# 4_-_Ethernet_PHY.net
KiCad netlist of a schematic drawn in Altium Designer
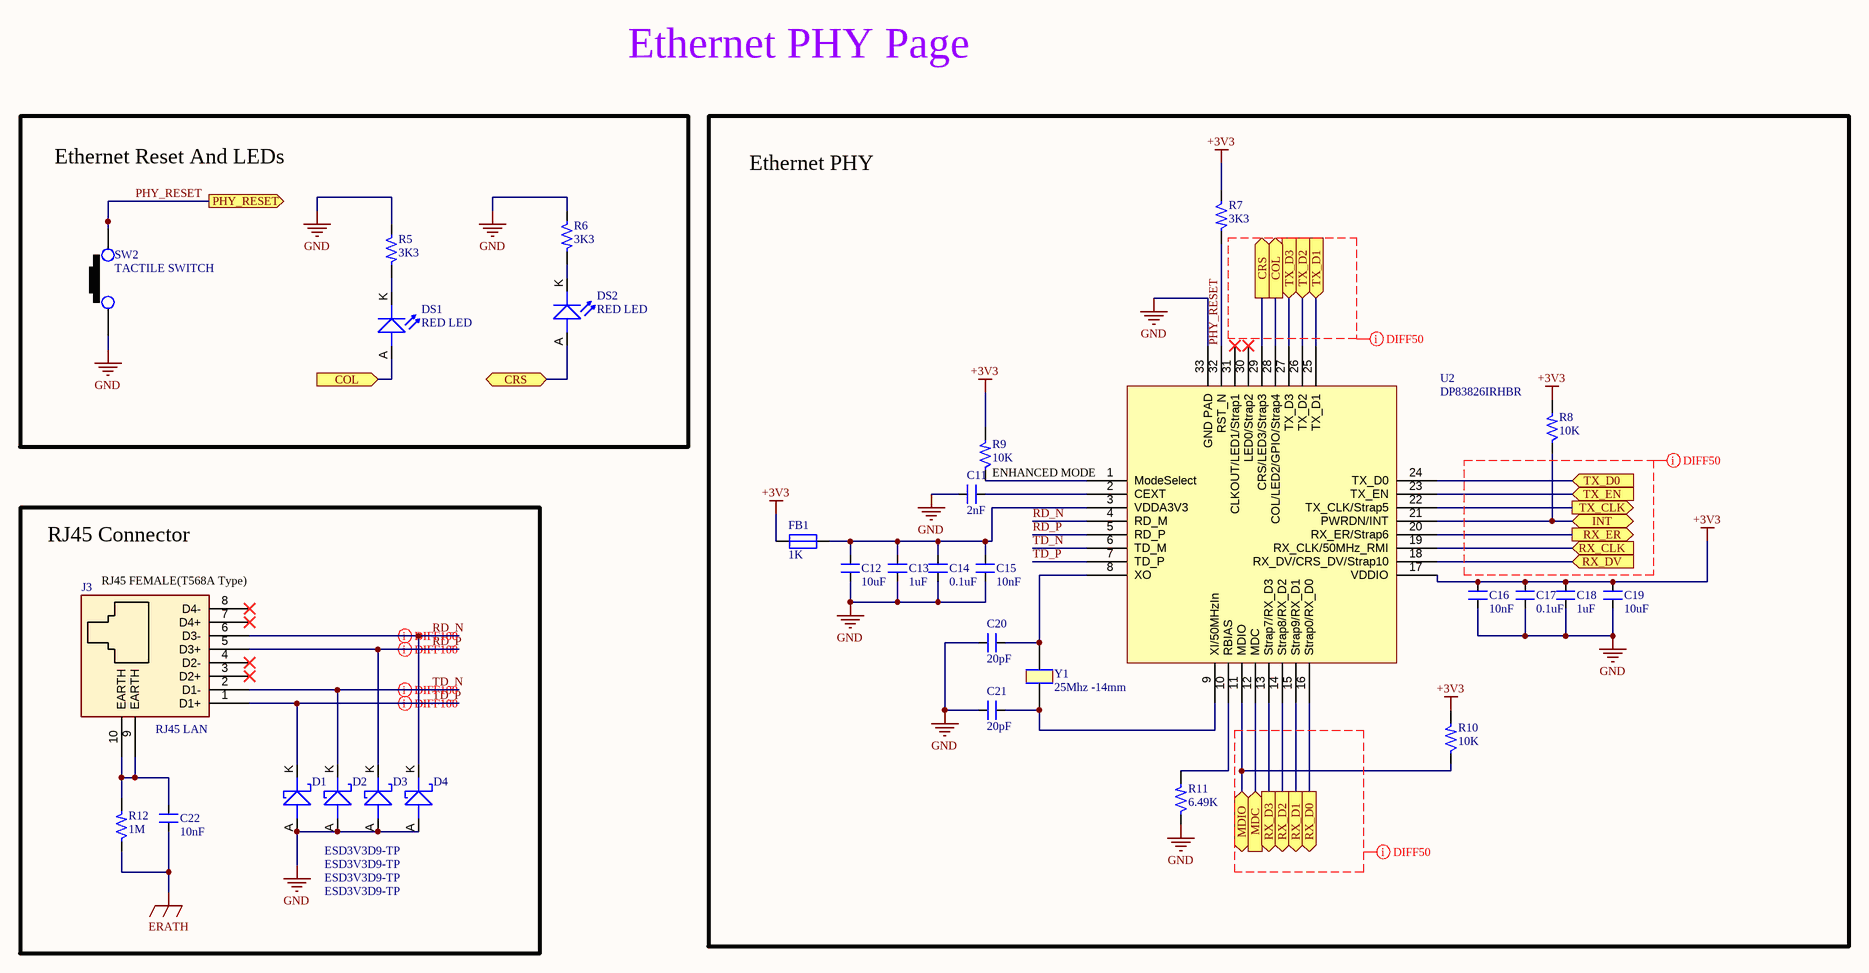
[diagram p0: [4] - Ethernet PHY.SchDoc]

(export (version "E")
  (design (tool "Eeschema 10.0.6"))
  (components
    (comp (ref "C11")
      (value "2nF")
      (footprint "CAP_0805")
      (description "2000pF ±10% 50V Ceramic Capacitor X7R 0805 (2012 Metric)")
      (fields
        (field (name "MANUFACTURER") "Samsung Electro-Mechanics")
        (field (name "MANUFACTURER PART NUMBER") "CL21B202KBANNNC")
      )
      (libsource (lib "ESTEEMPCBLIB") (part "CAP_2nF-50V-10%-0805"))
    )
    (comp (ref "C12")
      (value "10uF")
      (footprint "CAP_1206")
      (description "10µF ±10% 50V Ceramic Capacitor X7R 1206 (3216 Metric)")
      (fields
        (field (name "MANUFACTURER") "KEMET")
        (field (name "MANUFACTURER PART NUMBER") "CL31B106KBHNNNE")
      )
      (libsource (lib "ESTEEMPCBLIB") (part "CAP_10uF-50V-10%-1206"))
    )
    (comp (ref "C13")
      (value "1uF")
      (footprint "CAP_0805")
      (description "1µF ±5% 50V Ceramic Capacitor X7R 0805 (2012 Metric)")
      (fields
        (field (name "MANUFACTURER") "Samsung")
        (field (name "MANUFACTURER PART NUMBER") "CC0805JKX7R9BB105")
      )
      (libsource (lib "ESTEEMPCBLIB") (part "CAP_1uF-50V-5%-0805"))
    )
    (comp (ref "C14")
      (value "0.1uF")
      (footprint "CAP_0805")
      (description "0.1µF ±10% 50V Ceramic Capacitor X7R 0805 (2012 Metric)")
      (fields
        (field (name "MANUFACTURER") "Samsung")
        (field (name "MANUFACTURER PART NUMBER") "CL21B104KBCNNNC")
      )
      (libsource (lib "ESTEEMPCBLIB") (part "CAP_0.1uF-50V-10%-0805"))
    )
    (comp (ref "C15")
      (value "10nF")
      (footprint "CAP_0805")
      (description "10000pF ±10% 50V Ceramic Capacitor X7R 0805 (2012 Metric)")
      (fields
        (field (name "MANUFACTURER") "Samsung")
        (field (name "MANUFACTURER PART NUMBER") "C0805C103K5RECAUTO")
      )
      (libsource (lib "ESTEEMPCBLIB") (part "CAP_10nF-50V-10%-0805"))
    )
    (comp (ref "C16")
      (value "10nF")
      (footprint "CAP_0805")
      (description "10000pF ±10% 50V Ceramic Capacitor X7R 0805 (2012 Metric)")
      (fields
        (field (name "MANUFACTURER") "Samsung")
        (field (name "MANUFACTURER PART NUMBER") "C0805C103K5RECAUTO")
      )
      (libsource (lib "ESTEEMPCBLIB") (part "CAP_10nF-50V-10%-0805"))
    )
    (comp (ref "C17")
      (value "0.1uF")
      (footprint "CAP_0805")
      (description "0.1µF ±10% 50V Ceramic Capacitor X7R 0805 (2012 Metric)")
      (fields
        (field (name "MANUFACTURER") "Samsung")
        (field (name "MANUFACTURER PART NUMBER") "CL21B104KBCNNNC")
      )
      (libsource (lib "ESTEEMPCBLIB") (part "CAP_0.1uF-50V-10%-0805"))
    )
    (comp (ref "C18")
      (value "1uF")
      (footprint "CAP_0805")
      (description "1µF ±5% 50V Ceramic Capacitor X7R 0805 (2012 Metric)")
      (fields
        (field (name "MANUFACTURER") "Samsung")
        (field (name "MANUFACTURER PART NUMBER") "CC0805JKX7R9BB105")
      )
      (libsource (lib "ESTEEMPCBLIB") (part "CAP_1uF-50V-5%-0805"))
    )
    (comp (ref "C19")
      (value "10uF")
      (footprint "CAP_1206")
      (description "10µF ±10% 50V Ceramic Capacitor X7R 1206 (3216 Metric)")
      (fields
        (field (name "MANUFACTURER") "KEMET")
        (field (name "MANUFACTURER PART NUMBER") "CL31B106KBHNNNE")
      )
      (libsource (lib "ESTEEMPCBLIB") (part "CAP_10uF-50V-10%-1206"))
    )
    (comp (ref "C20")
      (value "20pF")
      (footprint "CAP_0805")
      (description "±10% 50V Ceramic Capacitor C0G, NP0 0805 (2012 Metric)")
      (fields
        (field (name "MANUFACTURER") "AVX Corporation")
        (field (name "MANUFACTURER PART NUMBER") "08055A200KAT2A")
      )
      (libsource (lib "ESTEEMPCBLIB") (part "CAP_20pF-50V-10%-0805"))
    )
    (comp (ref "C21")
      (value "20pF")
      (footprint "CAP_0805")
      (description "±10% 50V Ceramic Capacitor C0G, NP0 0805 (2012 Metric)")
      (fields
        (field (name "MANUFACTURER") "AVX Corporation")
        (field (name "MANUFACTURER PART NUMBER") "08055A200KAT2A")
      )
      (libsource (lib "ESTEEMPCBLIB") (part "CAP_20pF-50V-10%-0805"))
    )
    (comp (ref "C22")
      (value "10nF")
      (footprint "CAP_P196_102X287_H332_RAD_TH")
      (description "10000pF ±10% 1000V (1kV) Ceramic Capacitor X7R Radial")
      (fields
        (field (name "MANUFACTURER") "Yageo")
        (field (name "MANUFACTURER PART NUMBER") "RDER73A103K2K1H03B")
      )
      (libsource (lib "ESTEEMPCBLIB") (part "CAP_10nF-1KV-10%-RAD-TH"))
    )
    (comp (ref "D1")
      (value "ESD3V3D9-TP")
      (footprint "DIO_SOD-923")
      (description "8.8V Clamp 5A (8/20µs) Ipp Tvs Diode Surface Mount SOD-923")
      (fields (field (name "MANUFACTURER") "Micro Commercial Co"))
      (libsource (lib "ESTEEMPCBLIB") (part "DIO-T_3.3V-8.8V-SOD923"))
    )
    (comp (ref "D2")
      (value "ESD3V3D9-TP")
      (footprint "DIO_SOD-923")
      (description "8.8V Clamp 5A (8/20µs) Ipp Tvs Diode Surface Mount SOD-923")
      (fields (field (name "MANUFACTURER") "Micro Commercial Co"))
      (libsource (lib "ESTEEMPCBLIB") (part "DIO-T_3.3V-8.8V-SOD923"))
    )
    (comp (ref "D3")
      (value "ESD3V3D9-TP")
      (footprint "DIO_SOD-923")
      (description "8.8V Clamp 5A (8/20µs) Ipp Tvs Diode Surface Mount SOD-923")
      (fields (field (name "MANUFACTURER") "Micro Commercial Co"))
      (libsource (lib "ESTEEMPCBLIB") (part "DIO-T_3.3V-8.8V-SOD923"))
    )
    (comp (ref "D4")
      (value "ESD3V3D9-TP")
      (footprint "DIO_SOD-923")
      (description "8.8V Clamp 5A (8/20µs) Ipp Tvs Diode Surface Mount SOD-923")
      (fields (field (name "MANUFACTURER") "Micro Commercial Co"))
      (libsource (lib "ESTEEMPCBLIB") (part "DIO-T_3.3V-8.8V-SOD923"))
    )
    (comp (ref "DS1")
      (value "RED LED")
      (footprint "LED_0805")
      (description "Red 631nm LED Indication - Discrete 2V 0805 (2012 Metric)")
      (fields
        (field (name "MANUFACTURER") "Vishay Lite-On")
        (field (name "MANUFACTURER PART NUMBER") "LTST-C171KRKT")
      )
      (libsource (lib "ESTEEMPCBLIB") (part "LED_RED-2V-20mA-0805"))
    )
    (comp (ref "DS2")
      (value "RED LED")
      (footprint "LED_0805")
      (description "Red 631nm LED Indication - Discrete 2V 0805 (2012 Metric)")
      (fields
        (field (name "MANUFACTURER") "Vishay Lite-On")
        (field (name "MANUFACTURER PART NUMBER") "LTST-C171KRKT")
      )
      (libsource (lib "ESTEEMPCBLIB") (part "LED_RED-2V-20mA-0805"))
    )
    (comp (ref "FB1")
      (value "1K")
      (footprint "IND_0805")
      (description "1 kOhms @ 100MHz 1 Power Line Ferrite Bead 0805 (2012 Metric) 1.6A")
      (fields
        (field (name "MANUFACTURER") "Laird")
        (field (name "MANUFACTURER PART NUMBER") "BLM21SP102SH1D")
      )
      (libsource (lib "ESTEEMPCBLIB") (part "FB_1K-100MHZ-1.6A-0805"))
    )
    (comp (ref "J3")
      (value "RJ45 LAN")
      (footprint "CON10_P106_RJ45_TH_ST")
      (description "8 Pins, 2 Row 2.54mm Pitch, right angle Connector, male")
      (fields
        (field (name "MANUFACTURER") "Assmann")
        (field (name "MANUFACTURER PART NUMBER") "A-2004-2-4-LPS-N-R")
      )
      (libsource (lib "ESTEEMPCBLIB") (part "CON-SKT-RJ_8C8P-RA-TH"))
    )
    (comp (ref "R5")
      (value "3K3")
      (footprint "RES_0603")
      (description "3.3 kOhms ±1% 0.1W, 1/10W Chip Resistor 0603 (1608 Metric) Automotive AEC-Q200 Thick Film")
      (fields (field (name "MANUFACTURER") "Wilson") (field (name "MANUFACTURER PART NUMBER") "WR06X3301FTL"))
      (libsource (lib "ESTEEMPCBLIB") (part "RES_3.3K-0.1W-1%-0603"))
    )
    (comp (ref "R6")
      (value "3K3")
      (footprint "RES_0603")
      (description "3.3 kOhms ±1% 0.1W, 1/10W Chip Resistor 0603 (1608 Metric) Automotive AEC-Q200 Thick Film")
      (fields (field (name "MANUFACTURER") "Wilson") (field (name "MANUFACTURER PART NUMBER") "WR06X3301FTL"))
      (libsource (lib "ESTEEMPCBLIB") (part "RES_3.3K-0.1W-1%-0603"))
    )
    (comp (ref "R7")
      (value "3K3")
      (footprint "RES_0603")
      (description "3.3 kOhms ±1% 0.1W, 1/10W Chip Resistor 0603 (1608 Metric) Automotive AEC-Q200 Thick Film")
      (fields (field (name "MANUFACTURER") "Wilson") (field (name "MANUFACTURER PART NUMBER") "WR06X3301FTL"))
      (libsource (lib "ESTEEMPCBLIB") (part "RES_3.3K-0.1W-1%-0603"))
    )
    (comp (ref "R8")
      (value "10K")
      (footprint "RES_0603")
      (description "10 kOhms ±1% 0.1W, 1/10W Chip Resistor 0603 (1608 Metric) Automotive AEC-Q200 Thick Film")
      (fields (field (name "MANUFACTURER") "Walsin") (field (name "MANUFACTURER PART NUMBER") "WR06X1002FTL"))
      (libsource (lib "ESTEEMPCBLIB") (part "RES_10K-0.1W-1%-0603"))
    )
    (comp (ref "R9")
      (value "10K")
      (footprint "RES_0603")
      (description "10 kOhms ±1% 0.1W, 1/10W Chip Resistor 0603 (1608 Metric) Automotive AEC-Q200 Thick Film")
      (fields (field (name "MANUFACTURER") "Walsin") (field (name "MANUFACTURER PART NUMBER") "WR06X1002FTL"))
      (libsource (lib "ESTEEMPCBLIB") (part "RES_10K-0.1W-1%-0603"))
    )
    (comp (ref "R10")
      (value "10K")
      (footprint "RES_0603")
      (description "10 kOhms ±1% 0.1W, 1/10W Chip Resistor 0603 (1608 Metric) Automotive AEC-Q200 Thick Film")
      (fields (field (name "MANUFACTURER") "Walsin") (field (name "MANUFACTURER PART NUMBER") "WR06X1002FTL"))
      (libsource (lib "ESTEEMPCBLIB") (part "RES_10K-0.1W-1%-0603"))
    )
    (comp (ref "R11")
      (value "6.49K")
      (footprint "RES_0805")
      (description "6.49 kOhms ±1% 0.125W, 1/8W Chip Resistor 0805 (2012 Metric) Moisture Resistant Thick Film")
      (fields
        (field (name "MANUFACTURER") "Stackpole Electronics")
        (field (name "MANUFACTURER PART NUMBER") "RC0805FR-076K49L")
      )
      (libsource (lib "ESTEEMPCBLIB") (part "RES_6.49K-0.125W-1%-0805"))
    )
    (comp (ref "R12")
      (value "1M")
      (footprint "RES_1206")
      (fields (field (name "MANUFACTURER") "Walsin") (field (name "MANUFACTURER PART NUMBER") "WR12X1004FTL"))
      (libsource (lib "ESTEEMPCBLIB") (part "RES_1M-0.25W-1%-1206"))
    )
    (comp (ref "SW2")
      (value "TACTILE SWITCH")
      (footprint "SW_342_SMD")
      (description "Tactile Switch SPST-NO Top Actuated Surface Mount")
      (fields
        (field (name "MANUFACTURER") "ITT C&K")
        (field (name "MANUFACTURER PART NUMBER") "RS-282G05A3-SMRT")
      )
      (libsource (lib "ESTEEMPCBLIB") (part "SW1_RS-282G05A3-SMRT-SMD"))
    )
    (comp (ref "U2")
      (value "DP83826IRHBR")
      (footprint "VQFN32_19_218_23X9_SMD")
      (fields (field (name "MANUFACTURER") "Texas Instruments"))
      (libsource (lib "ESTEEMPCBLIB") (part "IC_DP83826IRHBR"))
    )
    (comp (ref "Y1")
      (value "25Mhz -14mm")
      (footprint "XTAL_314_240X47_SMD")
      (description "25MHz ±30ppm Crystal 20pF 30 Ohms HC-49/US")
      (fields
        (field (name "MANUFACTURER") "Abracon")
        (field (name "MANUFACTURER PART NUMBER") "FOXSDLF/250F-20")
      )
      (libsource (lib "ESTEEMPCBLIB") (part "XTAL_25Mhz-FOXSDLF/250F-20"))
    )
  )
  (nets
    (net (code "1") (name "+3V3") (class "Default")
      (node (ref "C16") (pin "1") (pinfunction "1_1") (pintype "passive"))
      (node (ref "C17") (pin "1") (pinfunction "1_1") (pintype "passive"))
      (node (ref "C18") (pin "1") (pinfunction "1_1") (pintype "passive"))
      (node (ref "C19") (pin "1") (pinfunction "1_1") (pintype "passive"))
      (node (ref "FB1") (pin "1") (pinfunction "1_1") (pintype "passive"))
      (node (ref "R10") (pin "2") (pinfunction "2_2") (pintype "passive"))
      (node (ref "R7") (pin "1") (pinfunction "1_1") (pintype "passive"))
      (node (ref "R8") (pin "2") (pinfunction "2_2") (pintype "passive"))
      (node (ref "R9") (pin "2") (pinfunction "2_2") (pintype "passive"))
      (node (ref "U2") (pin "17") (pinfunction "VDDIO_17") (pintype "passive"))
    )
    (net (code "2") (name "/COL") (class "Default")
      (node (ref "DS1") (pin "A") (pinfunction "ANODE_A") (pintype "passive"))
      (node (ref "U2") (pin "28") (pinfunction "COL/LED2/GPIO/Strap4_28") (pintype "passive"))
    )
    (net (code "3") (name "/CRS") (class "Default")
      (node (ref "DS2") (pin "A") (pinfunction "ANODE_A") (pintype "passive"))
      (node (ref "U2") (pin "29") (pinfunction "CRS/LED3/Strap3_29") (pintype "passive"))
    )
    (net (code "4") (name "/INT") (class "Default")
      (node (ref "R8") (pin "1") (pinfunction "1_1") (pintype "passive"))
      (node (ref "U2") (pin "21") (pinfunction "PWRDN/INT_21") (pintype "passive"))
    )
    (net (code "5") (name "/MDC") (class "Default")
      (node (ref "U2") (pin "12") (pinfunction "MDC_12") (pintype "passive"))
    )
    (net (code "6") (name "/MDIO") (class "Default")
      (node (ref "R10") (pin "1") (pinfunction "1_1") (pintype "passive"))
      (node (ref "U2") (pin "11") (pinfunction "MDIO_11") (pintype "passive"))
    )
    (net (code "7") (name "/PHY_RESET") (class "Default")
      (node (ref "R7") (pin "2") (pinfunction "2_2") (pintype "passive"))
      (node (ref "SW2") (pin "2") (pinfunction "2_2") (pintype "passive"))
      (node (ref "U2") (pin "32") (pinfunction "RST_N_32") (pintype "passive"))
    )
    (net (code "8") (name "/RD_N") (class "Default")
      (node (ref "D4") (pin "K") (pinfunction "K_K") (pintype "passive"))
      (node (ref "J3") (pin "6") (pinfunction "D3-_6") (pintype "passive"))
      (node (ref "U2") (pin "4") (pinfunction "RD_M_4") (pintype "passive"))
    )
    (net (code "9") (name "/RD_P") (class "Default")
      (node (ref "D3") (pin "K") (pinfunction "K_K") (pintype "passive"))
      (node (ref "J3") (pin "5") (pinfunction "D3+_5") (pintype "passive"))
      (node (ref "U2") (pin "5") (pinfunction "RD_P_5") (pintype "passive"))
    )
    (net (code "10") (name "/RX_CLK") (class "Default")
      (node (ref "U2") (pin "19") (pinfunction "RX_CLK/50MHz_RMI_19") (pintype "passive"))
    )
    (net (code "11") (name "/RX_D0") (class "Default")
      (node (ref "U2") (pin "16") (pinfunction "Strap0/RX_D0_16") (pintype "passive"))
    )
    (net (code "12") (name "/RX_D1") (class "Default")
      (node (ref "U2") (pin "15") (pinfunction "Strap9/RX_D1_15") (pintype "passive"))
    )
    (net (code "13") (name "/RX_D2") (class "Default")
      (node (ref "U2") (pin "14") (pinfunction "Strap8/RX_D2_14") (pintype "passive"))
    )
    (net (code "14") (name "/RX_D3") (class "Default")
      (node (ref "U2") (pin "13") (pinfunction "Strap7/RX_D3_13") (pintype "passive"))
    )
    (net (code "15") (name "/RX_DV") (class "Default")
      (node (ref "U2") (pin "18") (pinfunction "RX_DV/CRS_DV/Strap10_18") (pintype "passive"))
    )
    (net (code "16") (name "/RX_ER") (class "Default")
      (node (ref "U2") (pin "20") (pinfunction "RX_ER/Strap6_20") (pintype "passive"))
    )
    (net (code "17") (name "/TD_N") (class "Default")
      (node (ref "D2") (pin "K") (pinfunction "K_K") (pintype "passive"))
      (node (ref "J3") (pin "2") (pinfunction "D1-_2") (pintype "passive"))
      (node (ref "U2") (pin "6") (pinfunction "TD_M_6") (pintype "passive"))
    )
    (net (code "18") (name "/TD_P") (class "Default")
      (node (ref "D1") (pin "K") (pinfunction "K_K") (pintype "passive"))
      (node (ref "J3") (pin "1") (pinfunction "D1+_1") (pintype "passive"))
      (node (ref "U2") (pin "7") (pinfunction "TD_P_7") (pintype "passive"))
    )
    (net (code "19") (name "/TX_CLK") (class "Default")
      (node (ref "U2") (pin "22") (pinfunction "TX_CLK/Strap5_22") (pintype "passive"))
    )
    (net (code "20") (name "/TX_D0") (class "Default")
      (node (ref "U2") (pin "24") (pinfunction "TX_D0_24") (pintype "passive"))
    )
    (net (code "21") (name "/TX_D1") (class "Default")
      (node (ref "U2") (pin "25") (pinfunction "TX_D1_25") (pintype "passive"))
    )
    (net (code "22") (name "/TX_D2") (class "Default")
      (node (ref "U2") (pin "26") (pinfunction "TX_D2_26") (pintype "passive"))
    )
    (net (code "23") (name "/TX_D3") (class "Default")
      (node (ref "U2") (pin "27") (pinfunction "TX_D3_27") (pintype "passive"))
    )
    (net (code "24") (name "/TX_EN") (class "Default")
      (node (ref "U2") (pin "23") (pinfunction "TX_EN_23") (pintype "passive"))
    )
    (net (code "25") (name "ERATH") (class "Default")
      (node (ref "C22") (pin "1") (pinfunction "1_1") (pintype "passive"))
      (node (ref "R12") (pin "1") (pinfunction "1_1") (pintype "passive"))
    )
    (net (code "26") (name "GND") (class "Default")
      (node (ref "C11") (pin "1") (pinfunction "1_1") (pintype "passive"))
      (node (ref "C12") (pin "1") (pinfunction "1_1") (pintype "passive"))
      (node (ref "C13") (pin "1") (pinfunction "1_1") (pintype "passive"))
      (node (ref "C14") (pin "1") (pinfunction "1_1") (pintype "passive"))
      (node (ref "C15") (pin "1") (pinfunction "1_1") (pintype "passive"))
      (node (ref "C16") (pin "2") (pinfunction "2_2") (pintype "passive"))
      (node (ref "C17") (pin "2") (pinfunction "2_2") (pintype "passive"))
      (node (ref "C18") (pin "2") (pinfunction "2_2") (pintype "passive"))
      (node (ref "C19") (pin "2") (pinfunction "2_2") (pintype "passive"))
      (node (ref "C20") (pin "1") (pinfunction "1_1") (pintype "passive"))
      (node (ref "C21") (pin "1") (pinfunction "1_1") (pintype "passive"))
      (node (ref "D1") (pin "A") (pinfunction "A_A") (pintype "passive"))
      (node (ref "D2") (pin "A") (pinfunction "A_A") (pintype "passive"))
      (node (ref "D3") (pin "A") (pinfunction "A_A") (pintype "passive"))
      (node (ref "D4") (pin "A") (pinfunction "A_A") (pintype "passive"))
      (node (ref "R11") (pin "1") (pinfunction "1_1") (pintype "passive"))
      (node (ref "R5") (pin "1") (pinfunction "1_1") (pintype "passive"))
      (node (ref "R6") (pin "1") (pinfunction "1_1") (pintype "passive"))
      (node (ref "SW2") (pin "1") (pinfunction "1_1") (pintype "passive"))
      (node (ref "U2") (pin "33") (pinfunction "GND_PAD_33") (pintype "passive"))
    )
    (net (code "27") (name "Net-(C22-Pad2)") (class "Default")
      (node (ref "C22") (pin "2") (pinfunction "2_2") (pintype "passive"))
      (node (ref "J3") (pin "10") (pinfunction "EARTH_10") (pintype "passive"))
      (node (ref "J3") (pin "9") (pinfunction "EARTH_9") (pintype "passive"))
      (node (ref "R12") (pin "2") (pinfunction "2_2") (pintype "passive"))
    )
    (net (code "28") (name "Net-(DS1-CATHODE)") (class "Default")
      (node (ref "DS1") (pin "K") (pinfunction "CATHODE_K") (pintype "passive"))
      (node (ref "R5") (pin "2") (pinfunction "2_2") (pintype "passive"))
    )
    (net (code "29") (name "Net-(DS2-CATHODE)") (class "Default")
      (node (ref "DS2") (pin "K") (pinfunction "CATHODE_K") (pintype "passive"))
      (node (ref "R6") (pin "2") (pinfunction "2_2") (pintype "passive"))
    )
    (net (code "30") (name "Net-(U2-CEXT)") (class "Default")
      (node (ref "C11") (pin "2") (pinfunction "2_2") (pintype "passive"))
      (node (ref "U2") (pin "2") (pinfunction "CEXT_2") (pintype "passive"))
    )
    (net (code "31") (name "Net-(U2-ModeSelect)") (class "Default")
      (node (ref "R9") (pin "1") (pinfunction "1_1") (pintype "passive"))
      (node (ref "U2") (pin "1") (pinfunction "ModeSelect_1") (pintype "passive"))
    )
    (net (code "32") (name "Net-(U2-RBIAS)") (class "Default")
      (node (ref "R11") (pin "2") (pinfunction "2_2") (pintype "passive"))
      (node (ref "U2") (pin "10") (pinfunction "RBIAS_10") (pintype "passive"))
    )
    (net (code "33") (name "Net-(U2-VDDA3V3)") (class "Default")
      (node (ref "C12") (pin "2") (pinfunction "2_2") (pintype "passive"))
      (node (ref "C13") (pin "2") (pinfunction "2_2") (pintype "passive"))
      (node (ref "C14") (pin "2") (pinfunction "2_2") (pintype "passive"))
      (node (ref "C15") (pin "2") (pinfunction "2_2") (pintype "passive"))
      (node (ref "FB1") (pin "2") (pinfunction "2_2") (pintype "passive"))
      (node (ref "U2") (pin "3") (pinfunction "VDDA3V3_3") (pintype "passive"))
    )
    (net (code "34") (name "Net-(U2-XI{slash}50MHzIn)") (class "Default")
      (node (ref "C21") (pin "2") (pinfunction "2_2") (pintype "passive"))
      (node (ref "U2") (pin "9") (pinfunction "XI/50MHzIn_9") (pintype "passive"))
      (node (ref "Y1") (pin "1") (pinfunction "1_1") (pintype "passive"))
    )
    (net (code "35") (name "Net-(U2-XO)") (class "Default")
      (node (ref "C20") (pin "2") (pinfunction "2_2") (pintype "passive"))
      (node (ref "U2") (pin "8") (pinfunction "XO_8") (pintype "passive"))
      (node (ref "Y1") (pin "2") (pinfunction "2_2") (pintype "passive"))
    )
    (net (code "36") (name "unconnected-(J3-D2+-Pad3)") (class "Default")
      (node (ref "J3") (pin "3") (pinfunction "D2+_3") (pintype "passive+no_connect"))
    )
    (net (code "37") (name "unconnected-(J3-D2--Pad4)") (class "Default")
      (node (ref "J3") (pin "4") (pinfunction "D2-_4") (pintype "passive+no_connect"))
    )
    (net (code "38") (name "unconnected-(J3-D4+-Pad7)") (class "Default")
      (node (ref "J3") (pin "7") (pinfunction "D4+_7") (pintype "passive+no_connect"))
    )
    (net (code "39") (name "unconnected-(J3-D4--Pad8)") (class "Default")
      (node (ref "J3") (pin "8") (pinfunction "D4-_8") (pintype "passive+no_connect"))
    )
    (net (code "40") (name "unconnected-(U2-CLKOUT{slash}LED1{slash}Strap1-Pad31)") (class "Default")
      (node (ref "U2") (pin "31") (pinfunction "CLKOUT/LED1/Strap1_31") (pintype "passive+no_connect"))
    )
    (net (code "41") (name "unconnected-(U2-LED0{slash}Strap2-Pad30)") (class "Default")
      (node (ref "U2") (pin "30") (pinfunction "LED0/Strap2_30") (pintype "passive+no_connect"))
    )
  )
)
